# Buck_converter.net
KiCad netlist of a schematic drawn in Altium Designer
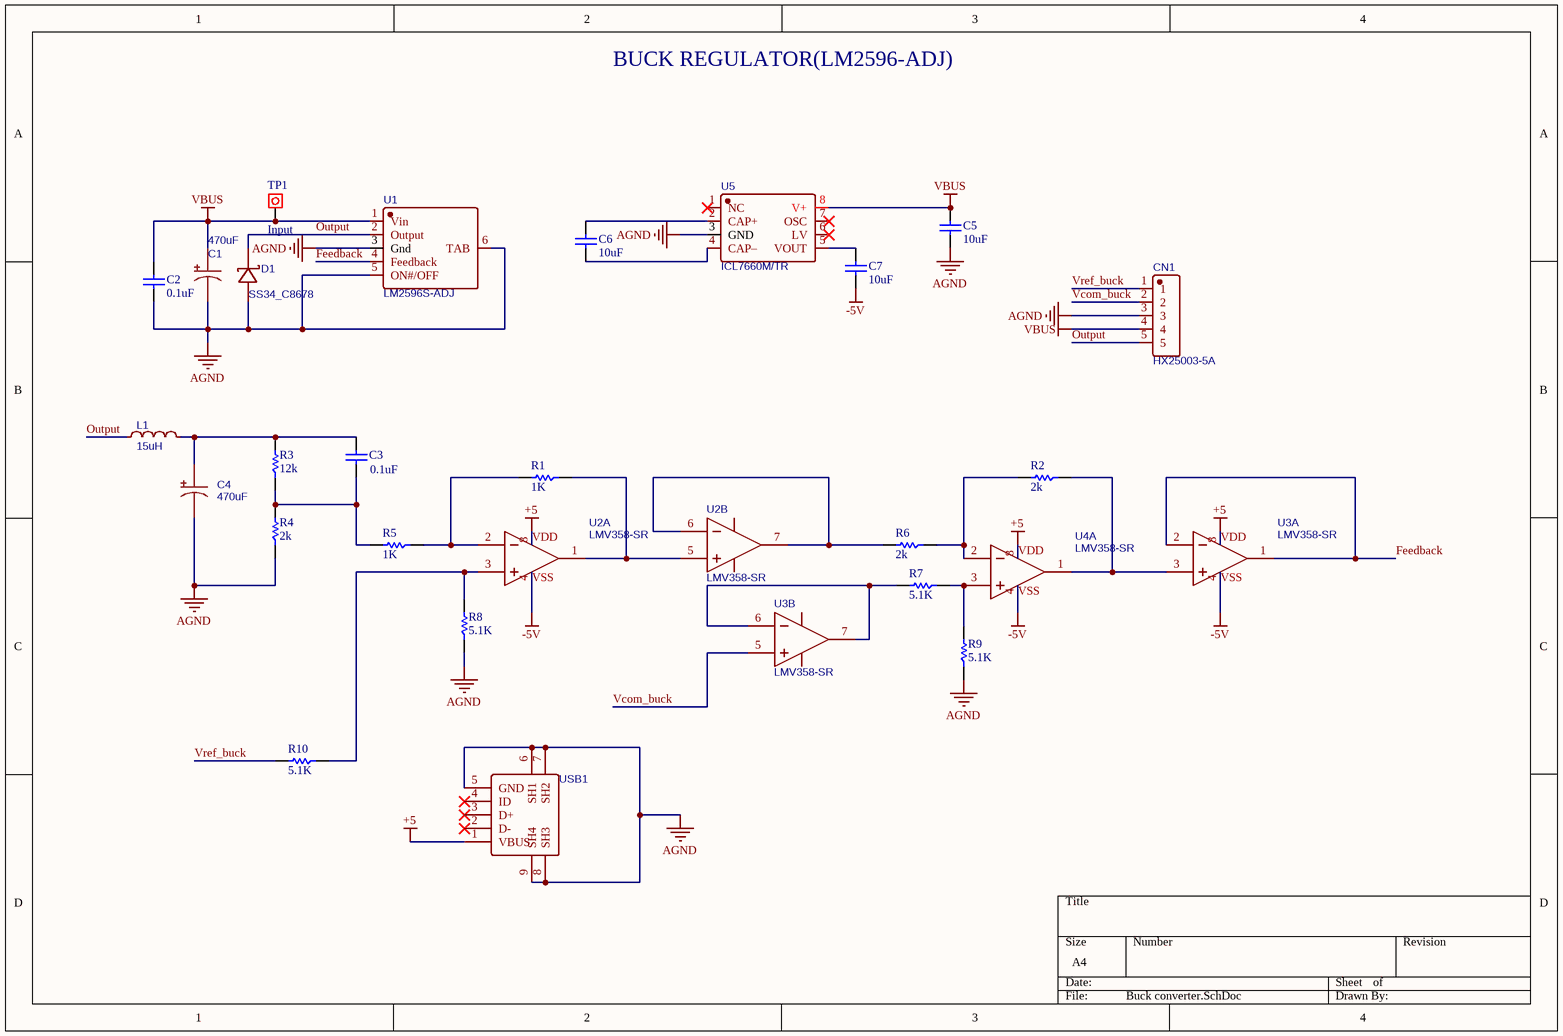
[diagram p0: Buck converter.SchDoc]

(export (version "E")
  (design (tool "Eeschema 10.0.6"))
  (components
    (comp (ref "C1")
      (value "470uF")
      (footprint "CAP-SMD_BD12.5-L13.0-W13.0-RD")
      (fields
        (field (name "BOM_MANUFACTURER PART") "RVT1H471M1213")
        (field (name "BOM_SUPPLIER PART") "C90272")
      )
      (libsource (lib "Portable power supply") (part "470uF"))
    )
    (comp (ref "C2")
      (value "0.1uF")
      (footprint "0805C")
      (description "Capacitor")
      (fields (field (name "REVIEWED BY") "RM - 2018/08/05"))
      (libsource (lib "Portable power supply") (part "C_0.1uf"))
    )
    (comp (ref "C3")
      (value "0.1uF")
      (footprint "0805C")
      (description "Capacitor")
      (fields (field (name "REVIEWED BY") "RM - 2018/08/05"))
      (libsource (lib "Portable power supply") (part "C_0.1uf"))
    )
    (comp (ref "C4")
      (value "470uF")
      (footprint "CAP-SMD_BD12.5-L13.0-W13.0-RD")
      (fields
        (field (name "BOM_MANUFACTURER PART") "RVT1H471M1213")
        (field (name "BOM_SUPPLIER PART") "C90272")
      )
      (libsource (lib "Portable power supply") (part "470uF"))
    )
    (comp (ref "C5")
      (value "10uF")
      (footprint "0805C")
      (description "Capacitor")
      (fields (field (name "REVIEWED BY") "RM - 2018/08/05"))
      (libsource (lib "Portable power supply") (part "C_10uf"))
    )
    (comp (ref "C6")
      (value "10uF")
      (footprint "0805C")
      (description "Capacitor")
      (fields (field (name "REVIEWED BY") "RM - 2018/08/05"))
      (libsource (lib "Portable power supply") (part "C_10uf"))
    )
    (comp (ref "C7")
      (value "10uF")
      (footprint "0805C")
      (description "Capacitor")
      (fields (field (name "REVIEWED BY") "RM - 2018/08/05"))
      (libsource (lib "Portable power supply") (part "C_10uf"))
    )
    (comp (ref "CN1")
      (value "HX25003-5A")
      (footprint "CONN-TH_5P-P2.50_HX25003-5A")
      (fields (field (name "BOM_SUPPLIER PART") "C442302") (field (name "CONTRIBUTOR") "LCSC"))
      (libsource (lib "Portable power supply") (part "HX25003-5A"))
    )
    (comp (ref "D1")
      (value "SS34_C8678")
      (footprint "DO-214AC_L4.3-W2.7-LS5.3-RD")
      (fields (field (name "BOM_MANUFACTURER PART") "SS34") (field (name "BOM_SUPPLIER PART") "C8678"))
      (libsource (lib "Portable power supply") (part "SS34_C8678"))
    )
    (comp (ref "L1")
      (value "15uH")
      (footprint "IND-SMD_L11.5-W10.5_MWSA1004")
      (fields
        (field (name "BOM_SUPPLIER PART") "C151872")
        (field (name "BOM_MANUFACTURER PART") "MWSA1004-150MT")
        (field (name "CONTRIBUTOR") "LCSC")
      )
      (libsource (lib "Portable power supply") (part "15uH"))
    )
    (comp (ref "R1")
      (value "1K")
      (footprint "0805")
      (description "Resistor")
      (fields (field (name "REVIEWED BY") "RM - 2018/08/05"))
      (libsource (lib "Portable power supply") (part "R_1k"))
    )
    (comp (ref "R2")
      (value "2k")
      (footprint "0805")
      (description "Resistor")
      (fields (field (name "REVIEWED BY") "RM - 2018/08/05"))
      (libsource (lib "Portable power supply") (part "R_2k"))
    )
    (comp (ref "R3")
      (value "12k")
      (footprint "0805")
      (description "Resistor")
      (fields (field (name "REVIEWED BY") "RM - 2018/08/05"))
      (libsource (lib "Portable power supply") (part "R_12k"))
    )
    (comp (ref "R4")
      (value "2k")
      (footprint "0805")
      (description "Resistor")
      (fields (field (name "REVIEWED BY") "RM - 2018/08/05"))
      (libsource (lib "Portable power supply") (part "R_2k"))
    )
    (comp (ref "R5")
      (value "1K")
      (footprint "0805")
      (description "Resistor")
      (fields (field (name "REVIEWED BY") "RM - 2018/08/05"))
      (libsource (lib "Portable power supply") (part "R_1k"))
    )
    (comp (ref "R6")
      (value "2k")
      (footprint "0805")
      (description "Resistor")
      (fields (field (name "REVIEWED BY") "RM - 2018/08/05"))
      (libsource (lib "Portable power supply") (part "R_2k"))
    )
    (comp (ref "R7")
      (value "5.1K")
      (footprint "0805")
      (description "Resistor")
      (fields (field (name "REVIEWED BY") "RM - 2018/08/05"))
      (libsource (lib "Portable power supply") (part "R_5.1k"))
    )
    (comp (ref "R8")
      (value "5.1K")
      (footprint "0805")
      (description "Resistor")
      (fields (field (name "REVIEWED BY") "RM - 2018/08/05"))
      (libsource (lib "Portable power supply") (part "R_5.1k"))
    )
    (comp (ref "R9")
      (value "5.1K")
      (footprint "0805")
      (description "Resistor")
      (fields (field (name "REVIEWED BY") "RM - 2018/08/05"))
      (libsource (lib "Portable power supply") (part "R_5.1k"))
    )
    (comp (ref "R10")
      (value "5.1K")
      (footprint "0805")
      (description "Resistor")
      (fields (field (name "REVIEWED BY") "RM - 2018/08/05"))
      (libsource (lib "Portable power supply") (part "R_5.1k"))
    )
    (comp (ref "TP1")
      (value "Input")
      (footprint "Testpoin")
      (description "Pad")
      (fields (field (name "Comment") "INPUT"))
      (libsource (lib "Portable power supply") (part "Test Point"))
    )
    (comp (ref "U1")
      (value "LM2596S-ADJ")
      (footprint "TO-263-5_L10.2-W8.9-P1.70-BR")
      (fields (field (name "BOM_SUPPLIER PART") "C347423") (field (name "CONTRIBUTOR") "LCSC"))
      (libsource (lib "Portable power supply") (part "LM2596S-ADJ"))
    )
    (comp (ref "U2")
      (value "LMV358-SR")
      (footprint "SOP-8_L4.9-W3.9-P1.27-LS6.0-BL")
      (fields (field (name "BOM_SUPPLIER PART") "C362274") (field (name "SUBPART_NO") "2"))
      (libsource (lib "power supply ztc") (part "LMV358-SR"))
    )
    (comp (ref "U3")
      (value "LMV358-SR")
      (footprint "SOP-8_L4.9-W3.9-P1.27-LS6.0-BL")
      (fields (field (name "BOM_SUPPLIER PART") "C362274") (field (name "SUBPART_NO") "2"))
      (libsource (lib "power supply ztc") (part "LMV358-SR"))
    )
    (comp (ref "U4")
      (value "LMV358-SR")
      (footprint "SOP-8_L4.9-W3.9-P1.27-LS6.0-BL")
      (fields (field (name "BOM_SUPPLIER PART") "C362274") (field (name "SUBPART_NO") "2"))
      (libsource (lib "power supply ztc") (part "LMV358-SR"))
    )
    (comp (ref "U5")
      (value "ICL7660M/TR")
      (footprint "SOP-8_L4.9-W3.9-P1.27-LS6.0-BL")
      (fields (field (name "BOM_SUPPLIER PART") "C356724") (field (name "CONTRIBUTOR") "LCSC"))
      (libsource (lib "Portable power supply") (part "ICL7660M/TR"))
    )
    (comp (ref "USB1")
      (value "microUSB")
      (footprint "MICRO-USB-SMD_MICROXNJ")
      (fields
        (field (name "BOM_SUPPLIER PART") "C404969")
        (field (name "BOM_MANUFACTURER PART") "MicroXNJ")
        (field (name "CONTRIBUTOR") "LCSC")
      )
      (libsource (lib "Portable power supply") (part "MICROXNJ"))
    )
  )
  (nets
    (net (code "1") (name "+5") (class "Default")
      (node (ref "U2") (pin "8") (pinfunction "VDD_8") (pintype "power_in"))
      (node (ref "U3") (pin "8") (pinfunction "VDD_8") (pintype "power_in"))
      (node (ref "U4") (pin "8") (pinfunction "VDD_8") (pintype "power_in"))
      (node (ref "USB1") (pin "1") (pinfunction "VBUS_1") (pintype "passive"))
    )
    (net (code "2") (name "-5V") (class "Default")
      (node (ref "C7") (pin "2") (pinfunction "2_2") (pintype "passive"))
      (node (ref "U2") (pin "4") (pinfunction "VSS_4") (pintype "power_in"))
      (node (ref "U3") (pin "4") (pinfunction "VSS_4") (pintype "power_in"))
      (node (ref "U4") (pin "4") (pinfunction "VSS_4") (pintype "power_in"))
    )
    (net (code "3") (name "/Feedback") (class "Default")
      (node (ref "U1") (pin "4") (pinfunction "Feedback_4") (pintype "passive"))
      (node (ref "U3") (pin "1") (pinfunction "OUTA_1") (pintype "passive"))
      (node (ref "U3") (pin "2") (pinfunction "INA-_2") (pintype "passive"))
    )
    (net (code "4") (name "/Output") (class "Default")
      (node (ref "CN1") (pin "5") (pinfunction "5_5") (pintype "passive"))
      (node (ref "D1") (pin "1") (pinfunction "K_1") (pintype "passive"))
      (node (ref "L1") (pin "1") (pinfunction "1_1") (pintype "passive"))
      (node (ref "U1") (pin "2") (pinfunction "Output_2") (pintype "passive"))
    )
    (net (code "5") (name "/Vcom_buck") (class "Default")
      (node (ref "CN1") (pin "2") (pinfunction "2_2") (pintype "passive"))
      (node (ref "U3") (pin "5") (pinfunction "INB+_5") (pintype "passive"))
    )
    (net (code "6") (name "/Vref_buck") (class "Default")
      (node (ref "CN1") (pin "1") (pinfunction "1_1") (pintype "passive"))
      (node (ref "R10") (pin "2") (pintype "passive"))
    )
    (net (code "7") (name "AGND") (class "Default")
      (node (ref "C1") (pin "2") (pinfunction "2_2") (pintype "passive"))
      (node (ref "C2") (pin "2") (pinfunction "2_2") (pintype "passive"))
      (node (ref "C4") (pin "2") (pinfunction "2_2") (pintype "passive"))
      (node (ref "C5") (pin "2") (pinfunction "2_2") (pintype "passive"))
      (node (ref "CN1") (pin "3") (pinfunction "3_3") (pintype "passive"))
      (node (ref "D1") (pin "2") (pinfunction "A_2") (pintype "passive"))
      (node (ref "R4") (pin "1") (pintype "passive"))
      (node (ref "R8") (pin "1") (pintype "passive"))
      (node (ref "R9") (pin "1") (pintype "passive"))
      (node (ref "U1") (pin "3") (pinfunction "Gnd_3") (pintype "passive"))
      (node (ref "U1") (pin "5") (pinfunction "ON#/OFF_5") (pintype "passive"))
      (node (ref "U1") (pin "6") (pinfunction "TAB_6") (pintype "passive"))
      (node (ref "U5") (pin "3") (pinfunction "GND_3") (pintype "passive"))
      (node (ref "USB1") (pin "5") (pinfunction "GND_5") (pintype "passive"))
      (node (ref "USB1") (pin "6") (pinfunction "SH1_6") (pintype "passive"))
      (node (ref "USB1") (pin "7") (pinfunction "SH2_7") (pintype "passive"))
      (node (ref "USB1") (pin "8") (pinfunction "SH3_8") (pintype "passive"))
      (node (ref "USB1") (pin "9") (pinfunction "SH4_9") (pintype "passive"))
    )
    (net (code "8") (name "Net-(C3-Pad1)") (class "Default")
      (node (ref "C3") (pin "1") (pinfunction "1_1") (pintype "passive"))
      (node (ref "C4") (pin "1") (pinfunction "1_1") (pintype "passive"))
      (node (ref "L1") (pin "2") (pinfunction "2_2") (pintype "passive"))
      (node (ref "R3") (pin "2") (pintype "passive"))
    )
    (net (code "9") (name "Net-(C3-Pad2)") (class "Default")
      (node (ref "C3") (pin "2") (pinfunction "2_2") (pintype "passive"))
      (node (ref "R3") (pin "1") (pintype "passive"))
      (node (ref "R4") (pin "2") (pintype "passive"))
      (node (ref "R5") (pin "2") (pintype "passive"))
    )
    (net (code "10") (name "Net-(U2A-INA+)") (class "Default")
      (node (ref "R10") (pin "1") (pintype "passive"))
      (node (ref "R8") (pin "2") (pintype "passive"))
      (node (ref "U2") (pin "3") (pinfunction "INA+_3") (pintype "passive"))
    )
    (net (code "11") (name "Net-(U2A-INA-)") (class "Default")
      (node (ref "R1") (pin "2") (pintype "passive"))
      (node (ref "R5") (pin "1") (pintype "passive"))
      (node (ref "U2") (pin "2") (pinfunction "INA-_2") (pintype "passive"))
    )
    (net (code "12") (name "Net-(U2A-OUTA)") (class "Default")
      (node (ref "R1") (pin "1") (pintype "passive"))
      (node (ref "U2") (pin "1") (pinfunction "OUTA_1") (pintype "passive"))
      (node (ref "U2") (pin "5") (pinfunction "INB+_5") (pintype "passive"))
    )
    (net (code "13") (name "Net-(U2B-INB-)") (class "Default")
      (node (ref "R6") (pin "2") (pintype "passive"))
      (node (ref "U2") (pin "6") (pinfunction "INB-_6") (pintype "passive"))
      (node (ref "U2") (pin "7") (pinfunction "OUTB_7") (pintype "passive"))
    )
    (net (code "14") (name "Net-(U3A-INA+)") (class "Default")
      (node (ref "R2") (pin "1") (pintype "passive"))
      (node (ref "U3") (pin "3") (pinfunction "INA+_3") (pintype "passive"))
      (node (ref "U4") (pin "1") (pinfunction "OUTA_1") (pintype "passive"))
    )
    (net (code "15") (name "Net-(U3B-INB-)") (class "Default")
      (node (ref "R7") (pin "2") (pintype "passive"))
      (node (ref "U3") (pin "6") (pinfunction "INB-_6") (pintype "passive"))
      (node (ref "U3") (pin "7") (pinfunction "OUTB_7") (pintype "passive"))
    )
    (net (code "16") (name "Net-(U4A-INA+)") (class "Default")
      (node (ref "R7") (pin "1") (pintype "passive"))
      (node (ref "R9") (pin "2") (pintype "passive"))
      (node (ref "U4") (pin "3") (pinfunction "INA+_3") (pintype "passive"))
    )
    (net (code "17") (name "Net-(U4A-INA-)") (class "Default")
      (node (ref "R2") (pin "2") (pintype "passive"))
      (node (ref "R6") (pin "1") (pintype "passive"))
      (node (ref "U4") (pin "2") (pinfunction "INA-_2") (pintype "passive"))
    )
    (net (code "18") (name "Net-(U5-CAP+)") (class "Default")
      (node (ref "C6") (pin "1") (pinfunction "1_1") (pintype "passive"))
      (node (ref "U5") (pin "2") (pinfunction "CAP+_2") (pintype "passive"))
    )
    (net (code "19") (name "Net-(U5-CAP–)") (class "Default")
      (node (ref "C6") (pin "2") (pinfunction "2_2") (pintype "passive"))
      (node (ref "U5") (pin "4") (pinfunction "CAP–_4") (pintype "passive"))
    )
    (net (code "20") (name "Net-(U5-VOUT)") (class "Default")
      (node (ref "C7") (pin "1") (pinfunction "1_1") (pintype "passive"))
      (node (ref "U5") (pin "5") (pinfunction "VOUT_5") (pintype "passive"))
    )
    (net (code "21") (name "VBUS") (class "Default")
      (node (ref "C1") (pin "1") (pinfunction "1_1") (pintype "passive"))
      (node (ref "C2") (pin "1") (pinfunction "1_1") (pintype "passive"))
      (node (ref "C5") (pin "1") (pinfunction "1_1") (pintype "passive"))
      (node (ref "CN1") (pin "4") (pinfunction "4_4") (pintype "passive"))
      (node (ref "TP1") (pin "1") (pintype "passive"))
      (node (ref "U1") (pin "1") (pinfunction "Vin_1") (pintype "passive"))
      (node (ref "U5") (pin "8") (pinfunction "V+_8") (pintype "passive"))
    )
    (net (code "22") (name "unconnected-(U5-LV-Pad6)") (class "Default")
      (node (ref "U5") (pin "6") (pinfunction "LV_6") (pintype "passive+no_connect"))
    )
    (net (code "23") (name "unconnected-(U5-NC-Pad1)") (class "Default")
      (node (ref "U5") (pin "1") (pinfunction "NC_1") (pintype "passive+no_connect"))
    )
    (net (code "24") (name "unconnected-(U5-OSC-Pad7)") (class "Default")
      (node (ref "U5") (pin "7") (pinfunction "OSC_7") (pintype "passive+no_connect"))
    )
    (net (code "25") (name "unconnected-(USB1-D+-Pad3)") (class "Default")
      (node (ref "USB1") (pin "3") (pinfunction "D+_3") (pintype "passive+no_connect"))
    )
    (net (code "26") (name "unconnected-(USB1-D--Pad2)") (class "Default")
      (node (ref "USB1") (pin "2") (pinfunction "D-_2") (pintype "passive+no_connect"))
    )
    (net (code "27") (name "unconnected-(USB1-ID-Pad4)") (class "Default")
      (node (ref "USB1") (pin "4") (pinfunction "ID_4") (pintype "passive+no_connect"))
    )
  )
)
